# PM667x_OCXO.net
KiCad netlist of a schematic drawn in EAGLE
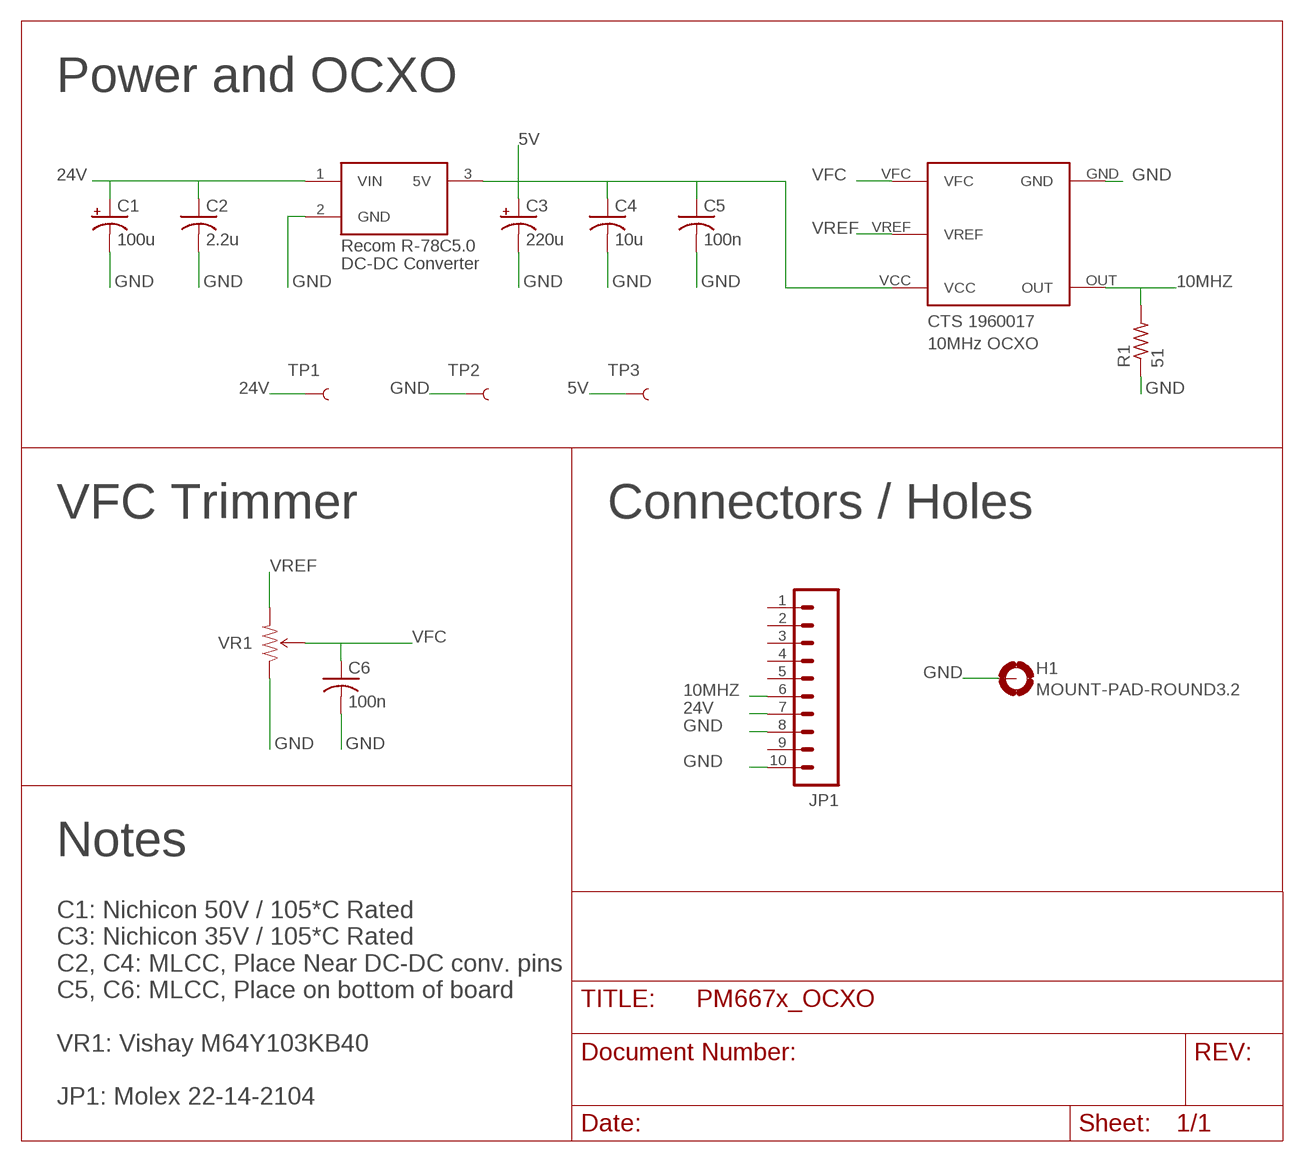
[diagram p0: schematic, sheet 1]

(export (version "E")
  (design (tool "Eeschema 10.0.6"))
  (components
    (comp (ref "C1")
      (value "100u")
      (footprint "eagle-import:E3,5-8")
      (libsource (lib "eagle-import") (part "CPOL-USE3.5-8"))
    )
    (comp (ref "C2")
      (value "2.2u")
      (footprint "eagle-import:C0805")
      (libsource (lib "eagle-import") (part "C-USC0805"))
    )
    (comp (ref "C3")
      (value "220u")
      (footprint "eagle-import:E3,5-8")
      (libsource (lib "eagle-import") (part "CPOL-USE3.5-8"))
    )
    (comp (ref "C4")
      (value "10u")
      (footprint "eagle-import:C0805")
      (libsource (lib "eagle-import") (part "C-USC0805"))
    )
    (comp (ref "C5")
      (value "100n")
      (footprint "eagle-import:C0603")
      (libsource (lib "eagle-import") (part "C-USC0603"))
    )
    (comp (ref "C6")
      (value "100n")
      (footprint "eagle-import:C0603")
      (libsource (lib "eagle-import") (part "C-USC0603"))
    )
    (comp (ref "H1")
      (value "MOUNT-PAD-ROUND3.2")
      (footprint "eagle-import:3,2-PAD")
      (libsource (lib "eagle-import") (part "MOUNT-PAD-ROUND3.2"))
    )
    (comp (ref "JP1")
      (value "M10NO_SILK_PTH_FEMALE")
      (footprint "eagle-import:1X10_NO_SILK")
      (libsource (lib "eagle-import") (part "M10NO_SILK_PTH_FEMALE"))
    )
    (comp (ref "R1")
      (value "51")
      (footprint "eagle-import:R1206")
      (libsource (lib "eagle-import") (part "R-US_R1206"))
    )
    (comp (ref "TP1")
      (value "TEST-POINT3X5")
      (footprint "eagle-import:PAD.03X.05")
      (libsource (lib "eagle-import") (part "TEST-POINT3X5"))
    )
    (comp (ref "TP2")
      (value "TEST-POINT3X5")
      (footprint "eagle-import:PAD.03X.05")
      (libsource (lib "eagle-import") (part "TEST-POINT3X5"))
    )
    (comp (ref "TP3")
      (value "TEST-POINT3X5")
      (footprint "eagle-import:PAD.03X.05")
      (libsource (lib "eagle-import") (part "TEST-POINT3X5"))
    )
    (comp (ref "U$1")
      (value "CTS1960017")
      (footprint "eagle-import:CTS1960017")
      (libsource (lib "eagle-import") (part "CTS1960017"))
    )
    (comp (ref "U$3")
      (value "R-78C5.0")
      (footprint "eagle-import:R-78C5.0")
      (libsource (lib "eagle-import") (part "R-78C5.0"))
    )
    (comp (ref "U$4")
      (value "TE_CB10_TRIMMER")
      (footprint "eagle-import:TE_CONNECTIVITY_CB10_TRIMMER")
      (libsource (lib "eagle-import") (part "TE_CB10_TRIMMER"))
    )
  )
  (nets
    (net (code "1") (name "/5V") (class "Default")
      (node (ref "C3") (pin "+") (pinfunction "+_+") (pintype "passive"))
      (node (ref "C4") (pin "1") (pinfunction "1_1") (pintype "passive"))
      (node (ref "C5") (pin "1") (pinfunction "1_1") (pintype "passive"))
      (node (ref "TP3") (pin "P$1") (pinfunction "1_P$1") (pintype "bidirectional"))
      (node (ref "U$1") (pin "VCC") (pinfunction "VCC_VCC") (pintype "bidirectional"))
      (node (ref "U$3") (pin "3") (pinfunction "5V_3") (pintype "bidirectional"))
    )
    (net (code "2") (name "/10MHZ") (class "Default")
      (node (ref "JP1") (pin "6") (pinfunction "6_6") (pintype "passive"))
      (node (ref "R1") (pin "2") (pinfunction "2_2") (pintype "passive"))
      (node (ref "U$1") (pin "OUT") (pinfunction "OUT_OUT") (pintype "bidirectional"))
    )
    (net (code "3") (name "/24V") (class "Default")
      (node (ref "C1") (pin "+") (pinfunction "+_+") (pintype "passive"))
      (node (ref "C2") (pin "1") (pinfunction "1_1") (pintype "passive"))
      (node (ref "JP1") (pin "7") (pinfunction "7_7") (pintype "passive"))
      (node (ref "TP1") (pin "P$1") (pinfunction "1_P$1") (pintype "bidirectional"))
      (node (ref "U$3") (pin "1") (pinfunction "VIN_1") (pintype "bidirectional"))
    )
    (net (code "4") (name "/GND") (class "Default")
      (node (ref "C1") (pin "-") (pinfunction "-_-") (pintype "passive"))
      (node (ref "C2") (pin "2") (pinfunction "2_2") (pintype "passive"))
      (node (ref "C3") (pin "-") (pinfunction "-_-") (pintype "passive"))
      (node (ref "C4") (pin "2") (pinfunction "2_2") (pintype "passive"))
      (node (ref "C5") (pin "2") (pinfunction "2_2") (pintype "passive"))
      (node (ref "C6") (pin "2") (pinfunction "2_2") (pintype "passive"))
      (node (ref "H1") (pin "B3,2") (pinfunction "MOUNT_B3,2") (pintype "passive"))
      (node (ref "JP1") (pin "10") (pinfunction "10_10") (pintype "passive"))
      (node (ref "JP1") (pin "8") (pinfunction "8_8") (pintype "passive"))
      (node (ref "R1") (pin "1") (pinfunction "1_1") (pintype "passive"))
      (node (ref "TP2") (pin "P$1") (pinfunction "1_P$1") (pintype "bidirectional"))
      (node (ref "U$1") (pin "GND") (pinfunction "GND_GND") (pintype "bidirectional"))
      (node (ref "U$3") (pin "2") (pinfunction "GND_2") (pintype "bidirectional"))
      (node (ref "U$4") (pin "A") (pinfunction "CCW_A") (pintype "passive"))
    )
    (net (code "5") (name "/VFC") (class "Default")
      (node (ref "C6") (pin "1") (pinfunction "1_1") (pintype "passive"))
      (node (ref "U$1") (pin "VFC") (pinfunction "VFC_VFC") (pintype "bidirectional"))
      (node (ref "U$4") (pin "B") (pinfunction "WIPER_B") (pintype "passive"))
    )
    (net (code "6") (name "/VREF") (class "Default")
      (node (ref "U$1") (pin "VREF") (pinfunction "VREF_VREF") (pintype "bidirectional"))
      (node (ref "U$4") (pin "C") (pinfunction "CW_C") (pintype "passive"))
    )
    (net (code "7") (name "unconnected-(JP1-Pad1)") (class "Default")
      (node (ref "JP1") (pin "1") (pinfunction "1_1") (pintype "passive"))
    )
    (net (code "8") (name "unconnected-(JP1-Pad2)") (class "Default")
      (node (ref "JP1") (pin "2") (pinfunction "2_2") (pintype "passive"))
    )
    (net (code "9") (name "unconnected-(JP1-Pad3)") (class "Default")
      (node (ref "JP1") (pin "3") (pinfunction "3_3") (pintype "passive"))
    )
    (net (code "10") (name "unconnected-(JP1-Pad4)") (class "Default")
      (node (ref "JP1") (pin "4") (pinfunction "4_4") (pintype "passive"))
    )
    (net (code "11") (name "unconnected-(JP1-Pad5)") (class "Default")
      (node (ref "JP1") (pin "5") (pinfunction "5_5") (pintype "passive"))
    )
    (net (code "12") (name "unconnected-(JP1-Pad9)") (class "Default")
      (node (ref "JP1") (pin "9") (pinfunction "9_9") (pintype "passive"))
    )
  )
)
